# 10001_msp430_bsl_programmer.net
KiCad netlist of a schematic drawn in EAGLE
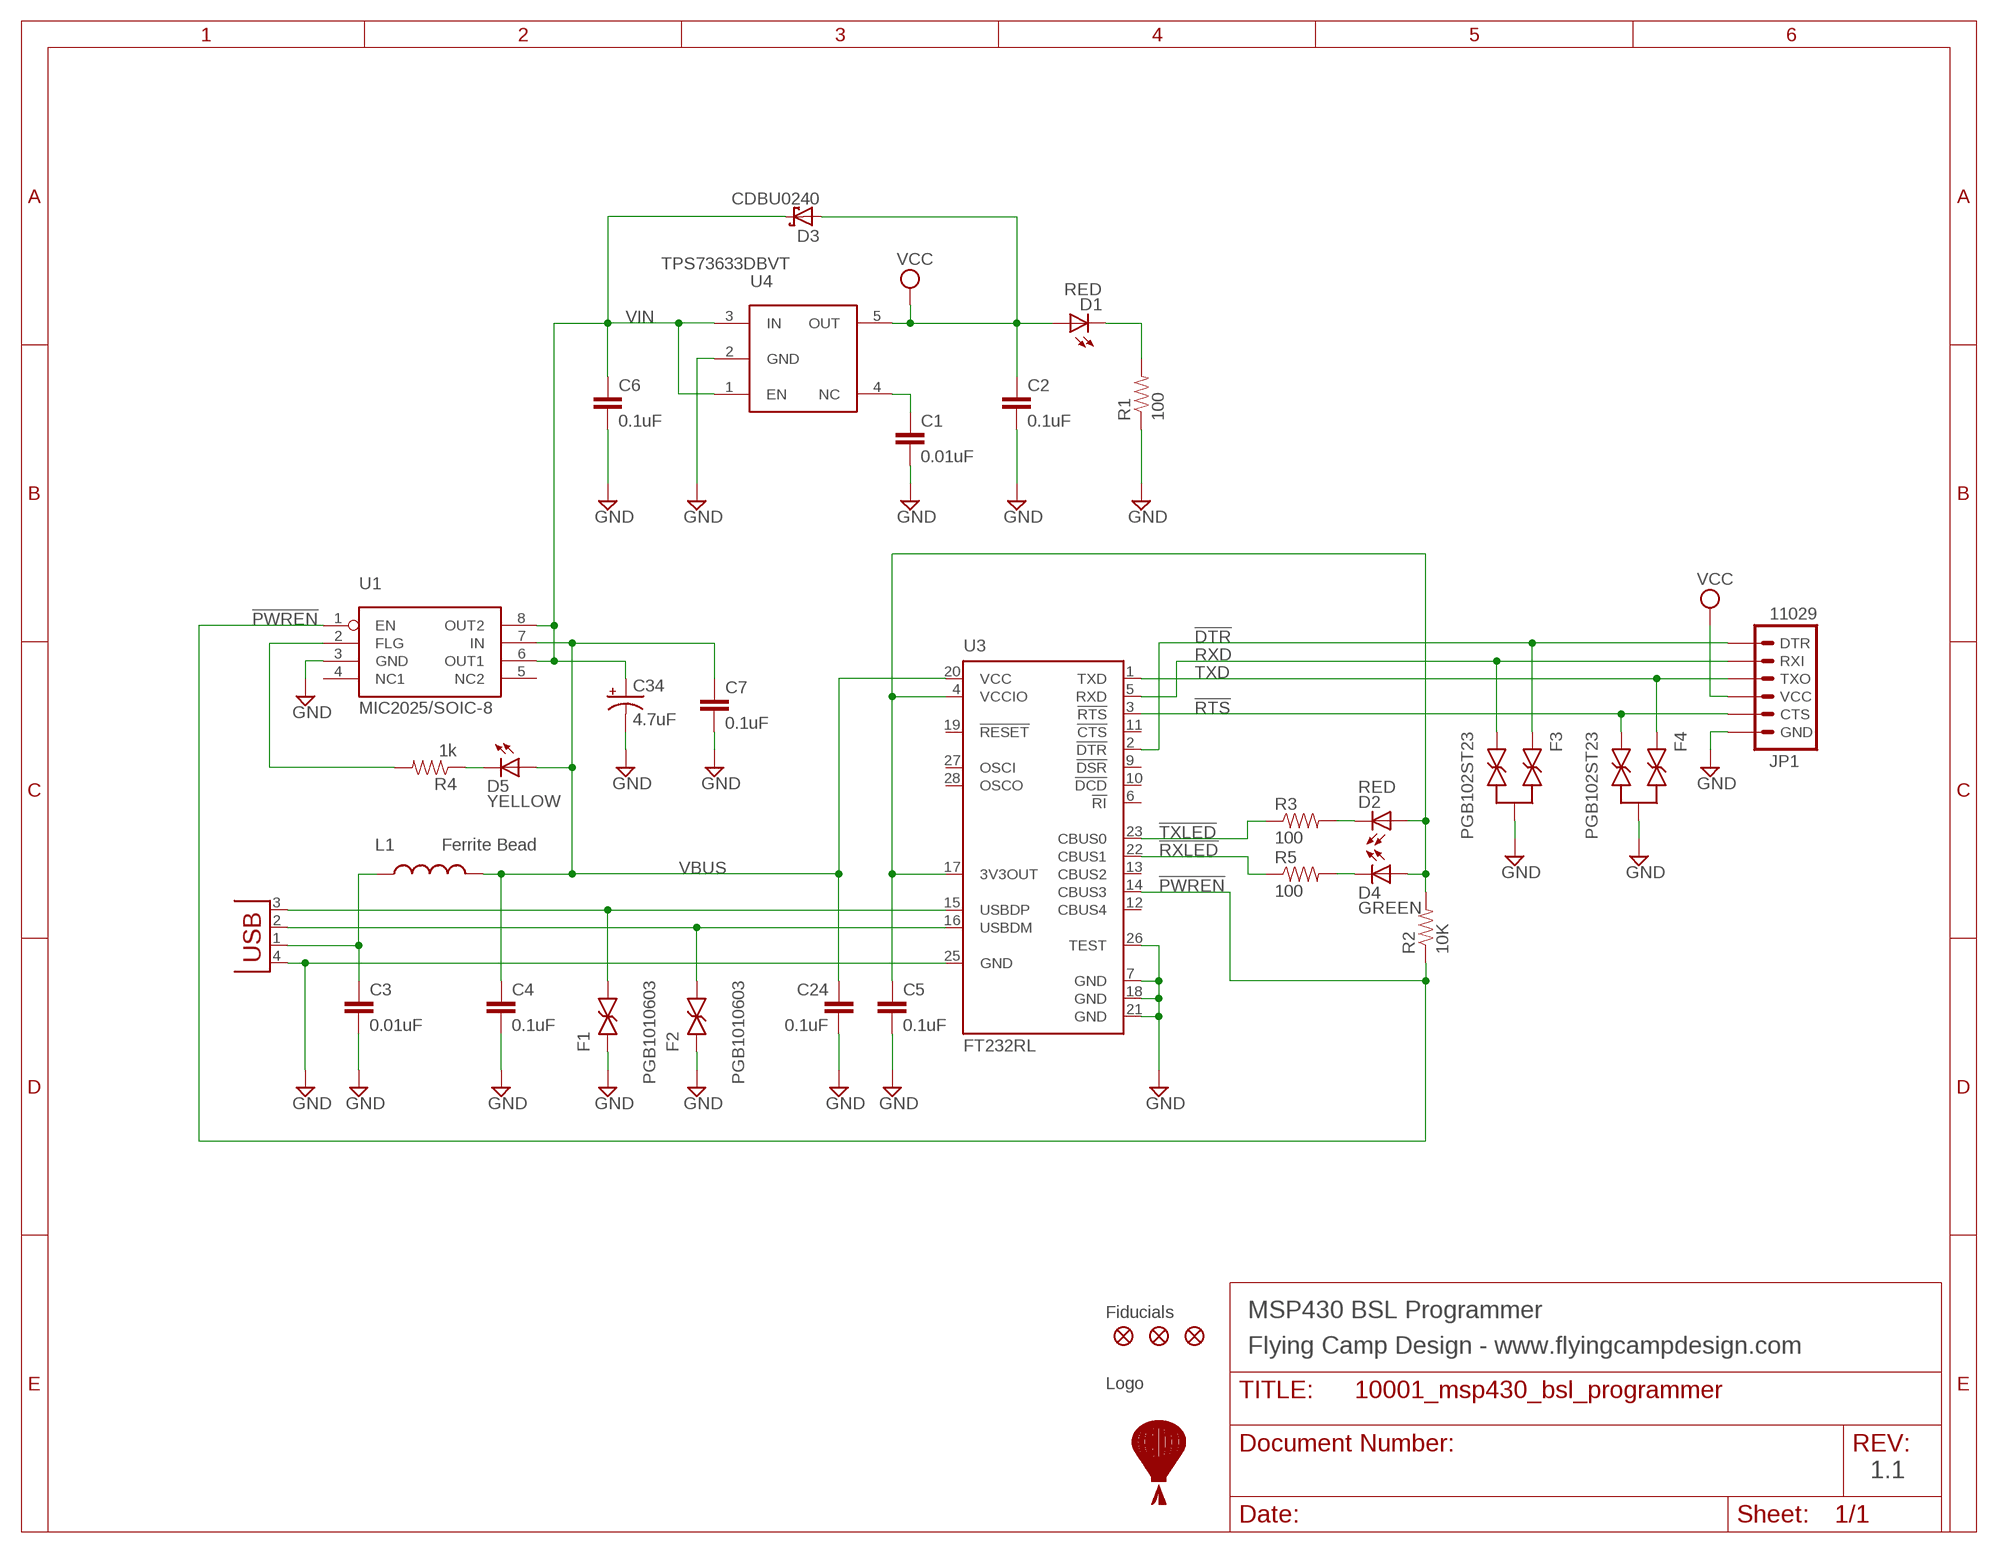
[diagram p0: schematic, sheet 1]

(export (version "E")
  (design (tool "Eeschema 10.0.6"))
  (components
    (comp (ref "C1")
      (value "0.01uF")
      (footprint "eagle-import:CAPC1608")
      (libsource (lib "eagle-import") (part "CAPACITOR1608"))
    )
    (comp (ref "C2")
      (value "0.1uF")
      (footprint "eagle-import:CAPC1608")
      (libsource (lib "eagle-import") (part "CAPACITOR1608"))
    )
    (comp (ref "C3")
      (value "0.01uF")
      (footprint "eagle-import:CAPC1608")
      (libsource (lib "eagle-import") (part "CAPACITOR1608"))
    )
    (comp (ref "C4")
      (value "0.1uF")
      (footprint "eagle-import:CAPC1608")
      (libsource (lib "eagle-import") (part "CAPACITOR1608"))
    )
    (comp (ref "C5")
      (value "0.1uF")
      (footprint "eagle-import:CAPC1608")
      (libsource (lib "eagle-import") (part "CAPACITOR1608"))
    )
    (comp (ref "C6")
      (value "0.1uF")
      (footprint "eagle-import:CAPC1608")
      (libsource (lib "eagle-import") (part "CAPACITOR1608"))
    )
    (comp (ref "C7")
      (value "0.1uF")
      (footprint "eagle-import:CAPC1608")
      (libsource (lib "eagle-import") (part "CAPACITOR1608"))
    )
    (comp (ref "C24")
      (value "0.1uF")
      (footprint "eagle-import:CAPC1608")
      (libsource (lib "eagle-import") (part "CAPACITOR1608"))
    )
    (comp (ref "C34")
      (value "4.7uF")
      (footprint "eagle-import:EIA3216")
      (libsource (lib "eagle-import") (part "CAP_POL1206"))
    )
    (comp (ref "D1")
      (value "RED")
      (footprint "eagle-import:LEDC1608")
      (libsource (lib "eagle-import") (part "LED1608"))
    )
    (comp (ref "D2")
      (value "RED")
      (footprint "eagle-import:LEDC1608")
      (libsource (lib "eagle-import") (part "LED1608"))
    )
    (comp (ref "D3")
      (value "CDBU0240")
      (footprint "eagle-import:D0603")
      (libsource (lib "eagle-import") (part "SCHOTTKY-DIODE0603"))
    )
    (comp (ref "D4")
      (value "GREEN")
      (footprint "eagle-import:LEDC1608")
      (libsource (lib "eagle-import") (part "LED1608"))
    )
    (comp (ref "D5")
      (value "YELLOW")
      (footprint "eagle-import:LEDC1608")
      (libsource (lib "eagle-import") (part "LED1608"))
    )
    (comp (ref "F1")
      (value "PGB1010603")
      (footprint "eagle-import:CAPC1608")
      (libsource (lib "eagle-import") (part "LITTELFUSE_PGB1010603"))
    )
    (comp (ref "F2")
      (value "PGB1010603")
      (footprint "eagle-import:CAPC1608")
      (libsource (lib "eagle-import") (part "LITTELFUSE_PGB1010603"))
    )
    (comp (ref "F3")
      (value "PGB102ST23")
      (footprint "eagle-import:SOT23")
      (libsource (lib "eagle-import") (part "LITTELFUSE_PGB102ST23"))
    )
    (comp (ref "F4")
      (value "PGB102ST23")
      (footprint "eagle-import:SOT23")
      (libsource (lib "eagle-import") (part "LITTELFUSE_PGB102ST23"))
    )
    (comp (ref "JP1")
      (value "11029")
      (footprint "eagle-import:1X06-SMD")
      (libsource (lib "eagle-import") (part "ARDUINO_SERIAL_PROGRAMSMD"))
    )
    (comp (ref "L1")
      (value "Ferrite Bead")
      (footprint "eagle-import:0603")
      (libsource (lib "eagle-import") (part "INDUCTOR0603"))
    )
    (comp (ref "P1")
      (value "MOLEX_48037-1000")
      (footprint "eagle-import:MOLEX_48037-1000")
      (libsource (lib "eagle-import") (part "MOLEX_48037-1000"))
    )
    (comp (ref "R1")
      (value "100")
      (footprint "eagle-import:RESC1608")
      (libsource (lib "eagle-import") (part "RESISTOR1608"))
    )
    (comp (ref "R2")
      (value "10K")
      (footprint "eagle-import:RESC1608")
      (libsource (lib "eagle-import") (part "RESISTOR1608"))
    )
    (comp (ref "R3")
      (value "100")
      (footprint "eagle-import:RESC1608")
      (libsource (lib "eagle-import") (part "RESISTOR1608"))
    )
    (comp (ref "R4")
      (value "1k")
      (footprint "eagle-import:RESC1608")
      (libsource (lib "eagle-import") (part "RESISTOR1608"))
    )
    (comp (ref "R5")
      (value "100")
      (footprint "eagle-import:RESC1608")
      (libsource (lib "eagle-import") (part "RESISTOR1608"))
    )
    (comp (ref "U$1")
      (value "FLYING_CAMP_DESIGN_LOGO")
      (footprint "eagle-import:FLYING_CAMP_DESIGN_LOGO")
      (libsource (lib "eagle-import") (part "FLYING_CAMP_DESIGN_LOGO"))
    )
    (comp (ref "U$2")
      (value "FIDUCIAL1X2")
      (footprint "eagle-import:FIDUCIAL-1X2")
      (libsource (lib "eagle-import") (part "FIDUCIAL1X2"))
    )
    (comp (ref "U$3")
      (value "FIDUCIAL1X2")
      (footprint "eagle-import:FIDUCIAL-1X2")
      (libsource (lib "eagle-import") (part "FIDUCIAL1X2"))
    )
    (comp (ref "U$4")
      (value "FIDUCIAL1X2")
      (footprint "eagle-import:FIDUCIAL-1X2")
      (libsource (lib "eagle-import") (part "FIDUCIAL1X2"))
    )
    (comp (ref "U1")
      (value "MIC2025/SOIC-8")
      (footprint "eagle-import:SOIC-8")
      (libsource (lib "eagle-import") (part "MIC2025/SOIC-8"))
    )
    (comp (ref "U3")
      (value "FT232RL")
      (footprint "eagle-import:SSOP28")
      (libsource (lib "eagle-import") (part "FT232RL"))
    )
    (comp (ref "U4")
      (value "TPS73633DBVT")
      (footprint "eagle-import:SOT95P280-5")
      (libsource (lib "eagle-import") (part "MIC5235SOT95P280-5"))
    )
  )
  (nets
    (net (code "1") (name "/RXD") (class "Default")
      (node (ref "F3") (pin "2") (pinfunction "2_2") (pintype "bidirectional"))
      (node (ref "JP1") (pin "2") (pinfunction "RXI_2") (pintype "passive"))
      (node (ref "U3") (pin "5") (pinfunction "RXD_5") (pintype "input"))
    )
    (net (code "2") (name "/TXD") (class "Default")
      (node (ref "F4") (pin "1") (pinfunction "1_1") (pintype "bidirectional"))
      (node (ref "JP1") (pin "3") (pinfunction "TXO_3") (pintype "passive"))
      (node (ref "U3") (pin "1") (pinfunction "TXD_1") (pintype "output"))
    )
    (net (code "3") (name "/VBUS") (class "Default")
      (node (ref "C24") (pin "1") (pinfunction "1_1") (pintype "passive"))
      (node (ref "C4") (pin "1") (pinfunction "1_1") (pintype "passive"))
      (node (ref "C7") (pin "1") (pinfunction "1_1") (pintype "passive"))
      (node (ref "D5") (pin "A") (pinfunction "A_A") (pintype "passive"))
      (node (ref "L1") (pin "2") (pinfunction "2_2") (pintype "passive"))
      (node (ref "U1") (pin "7") (pinfunction "IN_7") (pintype "power_in"))
      (node (ref "U3") (pin "20") (pinfunction "VCC_20") (pintype "power_in"))
    )
    (net (code "4") (name "/VIN") (class "Default")
      (node (ref "C34") (pin "A") (pinfunction "+_A") (pintype "passive"))
      (node (ref "C6") (pin "1") (pinfunction "1_1") (pintype "passive"))
      (node (ref "D3") (pin "C") (pinfunction "C_C") (pintype "passive"))
      (node (ref "U1") (pin "6") (pinfunction "OUT1_6") (pintype "power_in"))
      (node (ref "U1") (pin "8") (pinfunction "OUT2_8") (pintype "power_in"))
      (node (ref "U4") (pin "1") (pinfunction "EN_1") (pintype "bidirectional"))
      (node (ref "U4") (pin "3") (pinfunction "IN_3") (pintype "bidirectional"))
    )
    (net (code "5") (name "/~{DTR}") (class "Default")
      (node (ref "F3") (pin "1") (pinfunction "1_1") (pintype "bidirectional"))
      (node (ref "JP1") (pin "1") (pinfunction "DTR_1") (pintype "passive"))
      (node (ref "U3") (pin "2") (pinfunction "~{DTR}_2") (pintype "output"))
    )
    (net (code "6") (name "/~{PWREN}") (class "Default")
      (node (ref "R2") (pin "1") (pinfunction "1_1") (pintype "passive"))
      (node (ref "U1") (pin "1") (pinfunction "EN_1") (pintype "input"))
      (node (ref "U3") (pin "14") (pinfunction "CBUS3_14") (pintype "bidirectional"))
    )
    (net (code "7") (name "/~{RTS}") (class "Default")
      (node (ref "F4") (pin "2") (pinfunction "2_2") (pintype "bidirectional"))
      (node (ref "JP1") (pin "5") (pinfunction "CTS_5") (pintype "passive"))
      (node (ref "U3") (pin "3") (pinfunction "~{RTS}_3") (pintype "output"))
    )
    (net (code "8") (name "/~{RXLED}") (class "Default")
      (node (ref "R5") (pin "1") (pinfunction "1_1") (pintype "passive"))
      (node (ref "U3") (pin "22") (pinfunction "CBUS1_22") (pintype "bidirectional"))
    )
    (net (code "9") (name "/~{TXLED}") (class "Default")
      (node (ref "R3") (pin "1") (pinfunction "1_1") (pintype "passive"))
      (node (ref "U3") (pin "23") (pinfunction "CBUS0_23") (pintype "bidirectional"))
    )
    (net (code "10") (name "GND") (class "Default")
      (node (ref "C1") (pin "2") (pinfunction "2_2") (pintype "passive"))
      (node (ref "C2") (pin "2") (pinfunction "2_2") (pintype "passive"))
      (node (ref "C24") (pin "2") (pinfunction "2_2") (pintype "passive"))
      (node (ref "C3") (pin "2") (pinfunction "2_2") (pintype "passive"))
      (node (ref "C34") (pin "C") (pinfunction "-_C") (pintype "passive"))
      (node (ref "C4") (pin "2") (pinfunction "2_2") (pintype "passive"))
      (node (ref "C5") (pin "2") (pinfunction "2_2") (pintype "passive"))
      (node (ref "C6") (pin "2") (pinfunction "2_2") (pintype "passive"))
      (node (ref "C7") (pin "2") (pinfunction "2_2") (pintype "passive"))
      (node (ref "F1") (pin "1") (pinfunction "1_1") (pintype "bidirectional"))
      (node (ref "F2") (pin "1") (pinfunction "1_1") (pintype "bidirectional"))
      (node (ref "F3") (pin "3") (pinfunction "3_3") (pintype "bidirectional"))
      (node (ref "F4") (pin "3") (pinfunction "3_3") (pintype "bidirectional"))
      (node (ref "JP1") (pin "6") (pinfunction "GND_6") (pintype "passive"))
      (node (ref "P1") (pin "4") (pinfunction "GND_4") (pintype "bidirectional"))
      (node (ref "R1") (pin "1") (pinfunction "1_1") (pintype "passive"))
      (node (ref "U1") (pin "3") (pinfunction "GND_3") (pintype "power_in"))
      (node (ref "U3") (pin "18") (pinfunction "GND_18") (pintype "power_in"))
      (node (ref "U3") (pin "21") (pinfunction "GND_21") (pintype "power_in"))
      (node (ref "U3") (pin "25") (pinfunction "GND_25") (pintype "power_in"))
      (node (ref "U3") (pin "26") (pinfunction "TEST_26") (pintype "input"))
      (node (ref "U3") (pin "7") (pinfunction "GND_7") (pintype "power_in"))
      (node (ref "U4") (pin "2") (pinfunction "GND_2") (pintype "bidirectional"))
    )
    (net (code "11") (name "Net-(D1-PadC)") (class "Default")
      (node (ref "D1") (pin "C") (pinfunction "C_C") (pintype "passive"))
      (node (ref "R1") (pin "2") (pinfunction "2_2") (pintype "passive"))
    )
    (net (code "12") (name "Net-(D2-PadC)") (class "Default")
      (node (ref "D2") (pin "C") (pinfunction "C_C") (pintype "passive"))
      (node (ref "R3") (pin "2") (pinfunction "2_2") (pintype "passive"))
    )
    (net (code "13") (name "Net-(D4-PadC)") (class "Default")
      (node (ref "D4") (pin "C") (pinfunction "C_C") (pintype "passive"))
      (node (ref "R5") (pin "2") (pinfunction "2_2") (pintype "passive"))
    )
    (net (code "14") (name "Net-(D5-PadC)") (class "Default")
      (node (ref "D5") (pin "C") (pinfunction "C_C") (pintype "passive"))
      (node (ref "R4") (pin "1") (pinfunction "1_1") (pintype "passive"))
    )
    (net (code "15") (name "Net-(P1-D+)") (class "Default")
      (node (ref "F1") (pin "2") (pinfunction "2_2") (pintype "bidirectional"))
      (node (ref "P1") (pin "3") (pinfunction "D+_3") (pintype "bidirectional"))
      (node (ref "U3") (pin "15") (pinfunction "USBDP_15") (pintype "bidirectional"))
    )
    (net (code "16") (name "Net-(P1-D-)") (class "Default")
      (node (ref "F2") (pin "2") (pinfunction "2_2") (pintype "bidirectional"))
      (node (ref "P1") (pin "2") (pinfunction "D-_2") (pintype "bidirectional"))
      (node (ref "U3") (pin "16") (pinfunction "USBDM_16") (pintype "bidirectional"))
    )
    (net (code "17") (name "Net-(P1-VBUS)") (class "Default")
      (node (ref "C3") (pin "1") (pinfunction "1_1") (pintype "passive"))
      (node (ref "L1") (pin "1") (pinfunction "1_1") (pintype "passive"))
      (node (ref "P1") (pin "1") (pinfunction "VBUS_1") (pintype "bidirectional"))
    )
    (net (code "18") (name "Net-(U1-FLG)") (class "Default")
      (node (ref "R4") (pin "2") (pinfunction "2_2") (pintype "passive"))
      (node (ref "U1") (pin "2") (pinfunction "FLG_2") (pintype "output"))
    )
    (net (code "19") (name "Net-(U3-3V3OUT)") (class "Default")
      (node (ref "C5") (pin "1") (pinfunction "1_1") (pintype "passive"))
      (node (ref "D2") (pin "A") (pinfunction "A_A") (pintype "passive"))
      (node (ref "D4") (pin "A") (pinfunction "A_A") (pintype "passive"))
      (node (ref "R2") (pin "2") (pinfunction "2_2") (pintype "passive"))
      (node (ref "U3") (pin "17") (pinfunction "3V3OUT_17") (pintype "output"))
      (node (ref "U3") (pin "4") (pinfunction "VCCIO_4") (pintype "power_in"))
    )
    (net (code "20") (name "Net-(U4-NC)") (class "Default")
      (node (ref "C1") (pin "1") (pinfunction "1_1") (pintype "passive"))
      (node (ref "U4") (pin "4") (pinfunction "NC_4") (pintype "bidirectional"))
    )
    (net (code "21") (name "VCC") (class "Default")
      (node (ref "C2") (pin "1") (pinfunction "1_1") (pintype "passive"))
      (node (ref "D1") (pin "A") (pinfunction "A_A") (pintype "passive"))
      (node (ref "D3") (pin "A") (pinfunction "A_A") (pintype "passive"))
      (node (ref "JP1") (pin "4") (pinfunction "VCC_4") (pintype "passive"))
      (node (ref "U4") (pin "5") (pinfunction "OUT_5") (pintype "bidirectional"))
    )
    (net (code "22") (name "unconnected-(U1-NC1-Pad4)") (class "Default")
      (node (ref "U1") (pin "4") (pinfunction "NC1_4") (pintype "no_connect"))
    )
    (net (code "23") (name "unconnected-(U1-NC2-Pad5)") (class "Default")
      (node (ref "U1") (pin "5") (pinfunction "NC2_5") (pintype "no_connect"))
    )
    (net (code "24") (name "unconnected-(U3-CBUS2-Pad13)") (class "Default")
      (node (ref "U3") (pin "13") (pinfunction "CBUS2_13") (pintype "bidirectional"))
    )
    (net (code "25") (name "unconnected-(U3-CBUS4-Pad12)") (class "Default")
      (node (ref "U3") (pin "12") (pinfunction "CBUS4_12") (pintype "bidirectional"))
    )
    (net (code "26") (name "unconnected-(U3-OSCI-Pad27)") (class "Default")
      (node (ref "U3") (pin "27") (pinfunction "OSCI_27") (pintype "input"))
    )
    (net (code "27") (name "unconnected-(U3-OSCO-Pad28)") (class "Default")
      (node (ref "U3") (pin "28") (pinfunction "OSCO_28") (pintype "output"))
    )
    (net (code "28") (name "unconnected-(U3-~{CTS}-Pad11)") (class "Default")
      (node (ref "U3") (pin "11") (pinfunction "~{CTS}_11") (pintype "input"))
    )
    (net (code "29") (name "unconnected-(U3-~{DCD}-Pad10)") (class "Default")
      (node (ref "U3") (pin "10") (pinfunction "~{DCD}_10") (pintype "input"))
    )
    (net (code "30") (name "unconnected-(U3-~{DSR}-Pad9)") (class "Default")
      (node (ref "U3") (pin "9") (pinfunction "~{DSR}_9") (pintype "input"))
    )
    (net (code "31") (name "unconnected-(U3-~{RESET}-Pad19)") (class "Default")
      (node (ref "U3") (pin "19") (pinfunction "~{RESET}_19") (pintype "input"))
    )
    (net (code "32") (name "unconnected-(U3-~{RI}-Pad6)") (class "Default")
      (node (ref "U3") (pin "6") (pinfunction "~{RI}_6") (pintype "input"))
    )
  )
)
